# Ethernet.net
KiCad netlist of a schematic drawn in Altium Designer
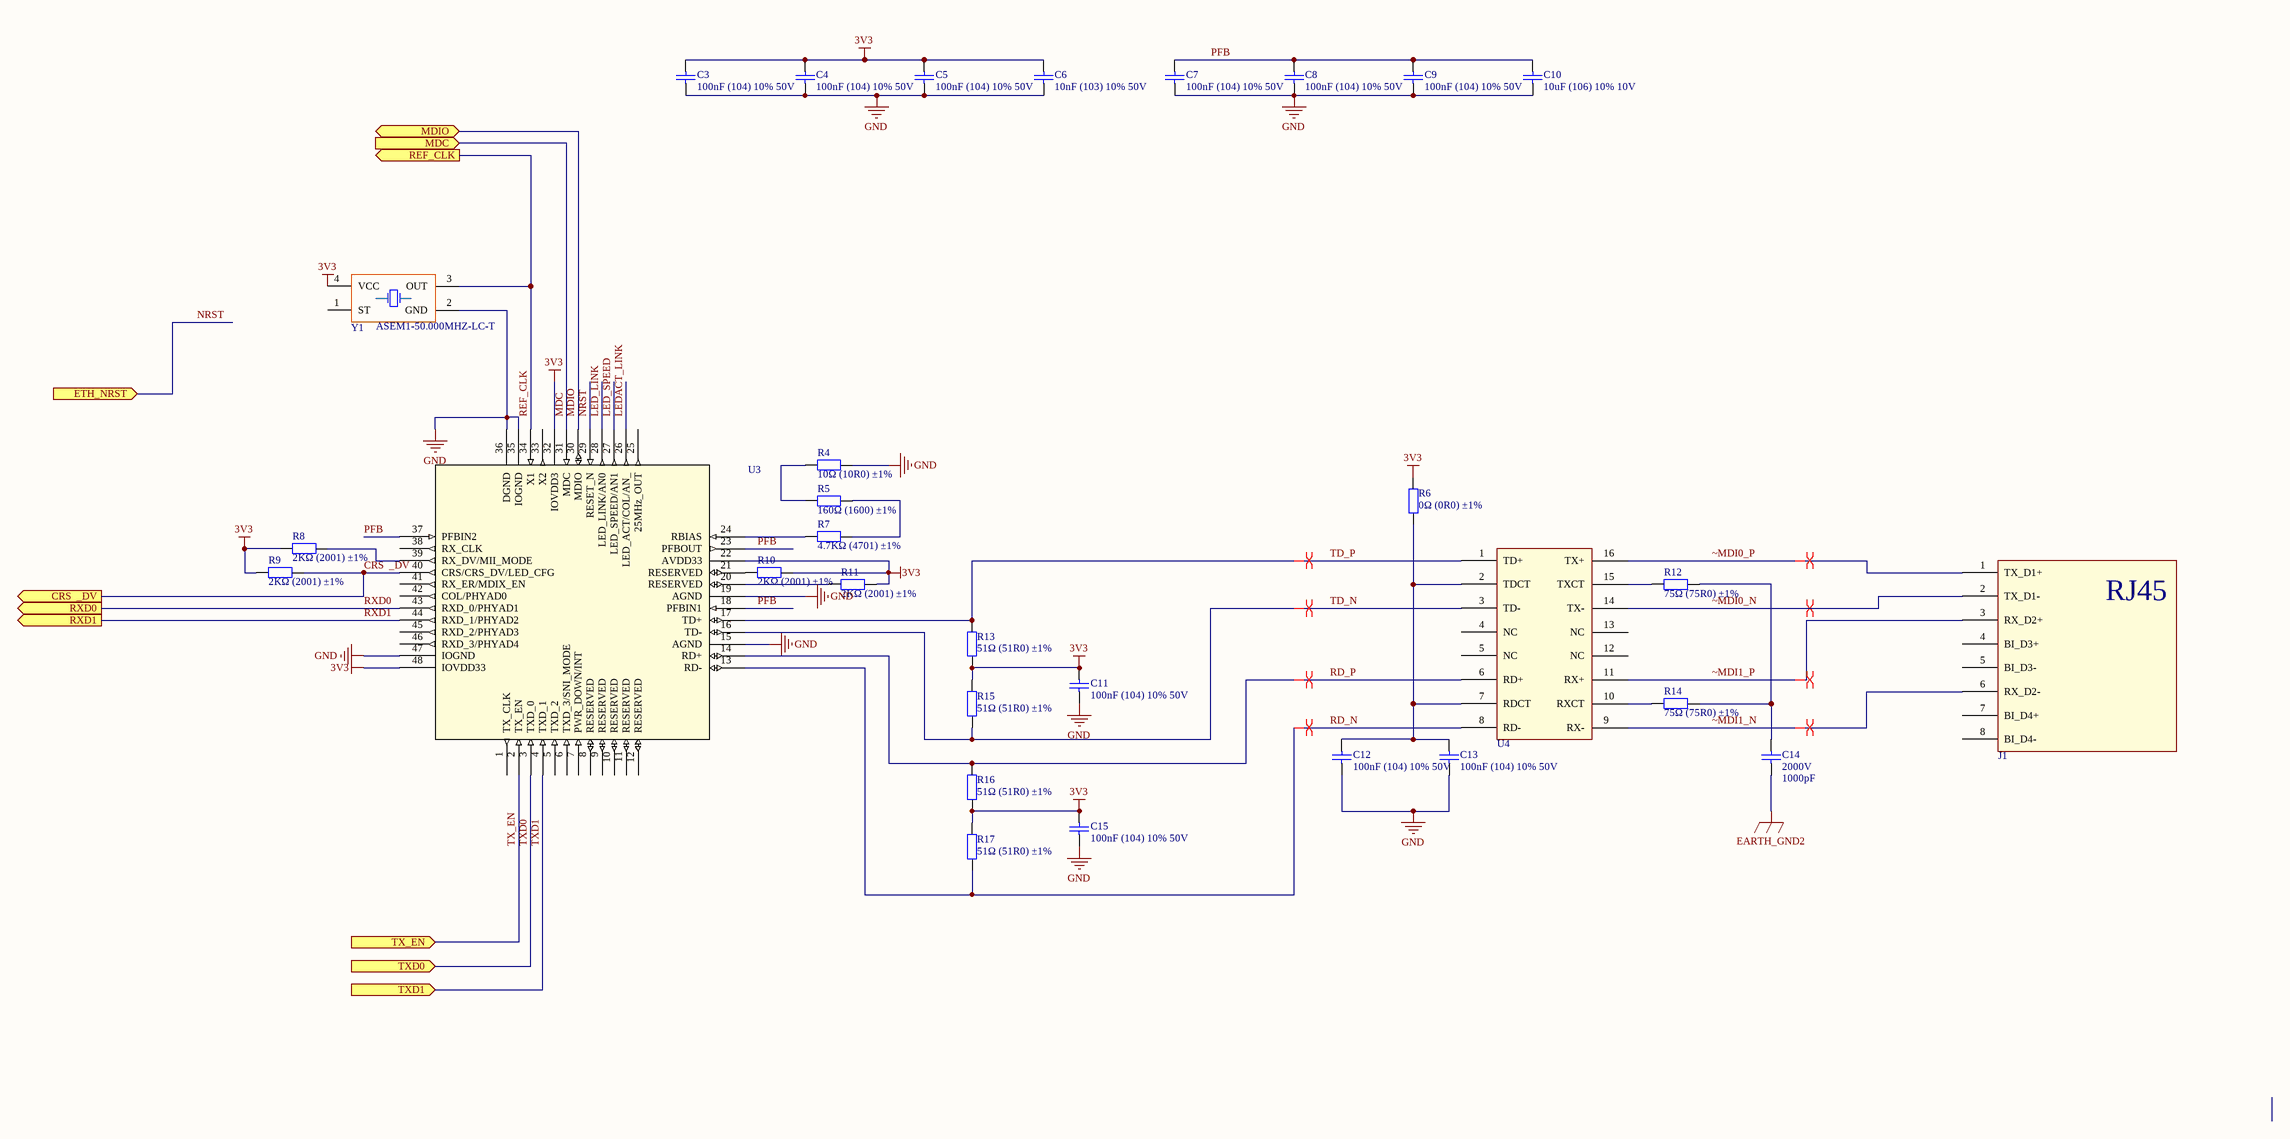
[diagram p0: Ethernet.SchDoc]

(export (version "E")
  (design (tool "Eeschema 10.0.6"))
  (components
    (comp (ref "C3")
      (value "100nF (104) 10% 50V")
      (footprint "0603_C")
      (description "贴片电容")
      (libsource (lib "Miscellaneous Devices LC") (part "0603 100nF (104) 10% 50V"))
    )
    (comp (ref "C4")
      (value "100nF (104) 10% 50V")
      (footprint "0603_C")
      (description "贴片电容")
      (libsource (lib "Miscellaneous Devices LC") (part "0603 100nF (104) 10% 50V"))
    )
    (comp (ref "C5")
      (value "100nF (104) 10% 50V")
      (footprint "0603_C")
      (description "贴片电容")
      (libsource (lib "Miscellaneous Devices LC") (part "0603 100nF (104) 10% 50V"))
    )
    (comp (ref "C6")
      (value "10nF (103) 10% 50V")
      (footprint "0603_C")
      (description "贴片电容")
      (libsource (lib "Miscellaneous Devices LC") (part "0603 10nF (103) 10% 50V"))
    )
    (comp (ref "C7")
      (value "100nF (104) 10% 50V")
      (footprint "0603_C")
      (description "贴片电容")
      (libsource (lib "Miscellaneous Devices LC") (part "0603 100nF (104) 10% 50V"))
    )
    (comp (ref "C8")
      (value "100nF (104) 10% 50V")
      (footprint "0603_C")
      (description "贴片电容")
      (libsource (lib "Miscellaneous Devices LC") (part "0603 100nF (104) 10% 50V"))
    )
    (comp (ref "C9")
      (value "100nF (104) 10% 50V")
      (footprint "0603_C")
      (description "贴片电容")
      (libsource (lib "Miscellaneous Devices LC") (part "0603 100nF (104) 10% 50V"))
    )
    (comp (ref "C10")
      (value "10uF (106) 10% 10V")
      (footprint "0603_C")
      (description "贴片电容")
      (libsource (lib "Miscellaneous Devices LC") (part "0603 10uF (106) 10% 10V"))
    )
    (comp (ref "C11")
      (value "100nF (104) 10% 50V")
      (footprint "0603_C")
      (description "贴片电容")
      (libsource (lib "Miscellaneous Devices LC") (part "0603 100nF (104) 10% 50V"))
    )
    (comp (ref "C12")
      (value "100nF (104) 10% 50V")
      (footprint "0603_C")
      (description "贴片电容")
      (libsource (lib "Miscellaneous Devices LC") (part "0603 100nF (104) 10% 50V"))
    )
    (comp (ref "C13")
      (value "100nF (104) 10% 50V")
      (footprint "0603_C")
      (description "贴片电容")
      (libsource (lib "Miscellaneous Devices LC") (part "0603 100nF (104) 10% 50V"))
    )
    (comp (ref "C14")
      (value "2000V")
      (footprint "CAP1210N")
      (description "CAP 1000pF ±10% 2000V (2kV) Ceramic Capacitor X7R 1210 (3225 Metric)")
      (fields
        (field (name "ALTIUM_VALUE") "1000pF")
        (field (name "MANUFACTURER") "Samsung Electro-Mechanics")
        (field (name "MANUFACTURER PART NUMBER") "CL32B102KJFNNNE")
      )
      (libsource (lib "RoboteX") (part "Cap Non-Polar"))
    )
    (comp (ref "C15")
      (value "100nF (104) 10% 50V")
      (footprint "0603_C")
      (description "贴片电容")
      (libsource (lib "Miscellaneous Devices LC") (part "0603 100nF (104) 10% 50V"))
    )
    (comp (ref "J1")
      (value "Jack Modular Connector 8p8c (RJ45, Ethernet) Vertical Unshielded Cat3")
      (footprint "RJ45-5556416-1")
      (description "RJ45 connector 180 degrees")
      (fields (field (name "PART NUMBER") "5556416-1") (field (name "MANUFACTURER") "TE"))
      (libsource (lib "RoboteX") (part "RJ45_180"))
    )
    (comp (ref "R4")
      (value "10Ω (10R0) ±1%")
      (footprint "0603_R")
      (description "贴片电阻")
      (libsource (lib "Miscellaneous Devices LC") (part "0603 10Ω (10R0) 1%"))
    )
    (comp (ref "R5")
      (value "160Ω (1600) ±1%")
      (footprint "0603_R")
      (description "贴片电阻")
      (libsource (lib "Miscellaneous Devices LC") (part "0603 160Ω (1600) 1%"))
    )
    (comp (ref "R6")
      (value "0Ω (0R0) ±1%")
      (footprint "0603_R")
      (description "贴片电阻")
      (libsource (lib "Miscellaneous Devices LC") (part "0603 0Ω (0R0) 1%"))
    )
    (comp (ref "R7")
      (value "4.7KΩ (4701) ±1%")
      (footprint "0603_R")
      (description "贴片电阻")
      (libsource (lib "Miscellaneous Devices LC") (part "0603 4.7KΩ (4701) 1%"))
    )
    (comp (ref "R8")
      (value "2KΩ (2001) ±1%")
      (footprint "0603_R")
      (description "贴片电阻")
      (libsource (lib "Miscellaneous Devices LC") (part "0603 2KΩ (2001) 1%"))
    )
    (comp (ref "R9")
      (value "2KΩ (2001) ±1%")
      (footprint "0603_R")
      (description "贴片电阻")
      (libsource (lib "Miscellaneous Devices LC") (part "0603 2KΩ (2001) 1%"))
    )
    (comp (ref "R10")
      (value "2KΩ (2001) ±1%")
      (footprint "0603_R")
      (description "贴片电阻")
      (libsource (lib "Miscellaneous Devices LC") (part "0603 2KΩ (2001) 1%"))
    )
    (comp (ref "R11")
      (value "2KΩ (2001) ±1%")
      (footprint "0603_R")
      (description "贴片电阻")
      (libsource (lib "Miscellaneous Devices LC") (part "0603 2KΩ (2001) 1%"))
    )
    (comp (ref "R12")
      (value "75Ω (75R0) ±1%")
      (footprint "0603_R")
      (description "贴片电阻")
      (libsource (lib "Miscellaneous Devices LC") (part "0603 75Ω (75R0) 1%"))
    )
    (comp (ref "R13")
      (value "51Ω (51R0) ±1%")
      (footprint "0603_R")
      (description "贴片电阻")
      (libsource (lib "Miscellaneous Devices LC") (part "0603 51Ω (51R0) 1%"))
    )
    (comp (ref "R14")
      (value "75Ω (75R0) ±1%")
      (footprint "0603_R")
      (description "贴片电阻")
      (libsource (lib "Miscellaneous Devices LC") (part "0603 75Ω (75R0) 1%"))
    )
    (comp (ref "R15")
      (value "51Ω (51R0) ±1%")
      (footprint "0603_R")
      (description "贴片电阻")
      (libsource (lib "Miscellaneous Devices LC") (part "0603 51Ω (51R0) 1%"))
    )
    (comp (ref "R16")
      (value "51Ω (51R0) ±1%")
      (footprint "0603_R")
      (description "贴片电阻")
      (libsource (lib "Miscellaneous Devices LC") (part "0603 51Ω (51R0) 1%"))
    )
    (comp (ref "R17")
      (value "51Ω (51R0) ±1%")
      (footprint "0603_R")
      (description "贴片电阻")
      (libsource (lib "Miscellaneous Devices LC") (part "0603 51Ω (51R0) 1%"))
    )
    (comp (ref "U3")
      (value "IC TXRX ETHERNET 48LQFP")
      (footprint "48-LQFP")
      (fields
        (field (name "PART NUMBER") "DP83848CVVX/NOPB")
        (field (name "MANUFACTURER") "Texas Instruments")
      )
      (libsource (lib "RoboteX") (part "DP83848CVV"))
    )
    (comp (ref "U4")
      (value "TRANSFORMER")
      (footprint "Bel_transformer")
      (description "MODULE XFRMR LAN 10/100B-TX SMD")
      (fields
        (field (name "MANUFACTURER") "Bel Fuse Inc.")
        (field (name "MANUFACTURER PART NUMBER") "S558-5999-U7-F")
      )
      (libsource (lib "RoboteX") (part "Transformer"))
    )
    (comp (ref "Y1")
      (value "Oscillator")
      (footprint "SMD-3225")
      (description "OSC MEMS 50.000MHZ CMOS SMD")
      (fields
        (field (name "PART NUMBER") "ASEM1-50.000MHZ-LC-T")
        (field (name "MANUFACTURER") "Abracon LLC")
        (field (name "MANUFACTURER PART NUMBER") "ASEM1-50.000MHZ-LC-T")
      )
      (libsource (lib "RoboteX") (part "SPXO"))
    )
  )
  (nets
    (net (code "1") (name "/CRS  _DV") (class "Default")
      (node (ref "R9") (pin "1") (pinfunction "1_1") (pintype "passive"))
      (node (ref "U3") (pin "40") (pinfunction "CRS/CRS_DV/LED_CFG_40") (pintype "output"))
    )
    (net (code "2") (name "/LEDACT_LINK") (class "Default")
      (node (ref "U3") (pin "26") (pinfunction "LED_ACT/COL/AN__26") (pintype "output"))
    )
    (net (code "3") (name "/LED_LINK") (class "Default")
      (node (ref "U3") (pin "28") (pinfunction "LED_LINK/AN0_28") (pintype "output"))
    )
    (net (code "4") (name "/LED_SPEED") (class "Default")
      (node (ref "U3") (pin "27") (pinfunction "LED_SPEED/AN1_27") (pintype "output"))
    )
    (net (code "5") (name "/MDC") (class "Default")
      (node (ref "U3") (pin "31") (pinfunction "MDC_31") (pintype "input"))
    )
    (net (code "6") (name "/MDIO") (class "Default")
      (node (ref "U3") (pin "30") (pinfunction "MDIO_30") (pintype "bidirectional"))
    )
    (net (code "7") (name "/NRST") (class "Default")
      (node (ref "U3") (pin "29") (pinfunction "RESET_N_29") (pintype "input"))
    )
    (net (code "8") (name "/PFB") (class "Default")
      (node (ref "C10") (pin "2") (pinfunction "2_2") (pintype "passive"))
      (node (ref "C7") (pin "2") (pinfunction "2_2") (pintype "passive"))
      (node (ref "C8") (pin "2") (pinfunction "2_2") (pintype "passive"))
      (node (ref "C9") (pin "2") (pinfunction "2_2") (pintype "passive"))
      (node (ref "U3") (pin "18") (pinfunction "PFBIN1_18") (pintype "input"))
      (node (ref "U3") (pin "23") (pinfunction "PFBOUT_23") (pintype "output"))
      (node (ref "U3") (pin "37") (pinfunction "PFBIN2_37") (pintype "input"))
    )
    (net (code "9") (name "/RD_N") (class "Default")
      (node (ref "R17") (pin "1") (pinfunction "1_1") (pintype "passive"))
      (node (ref "U3") (pin "13") (pinfunction "RD-_13") (pintype "bidirectional"))
      (node (ref "U4") (pin "8") (pinfunction "RD-_8") (pintype "passive"))
    )
    (net (code "10") (name "/RD_P") (class "Default")
      (node (ref "R16") (pin "2") (pinfunction "2_2") (pintype "passive"))
      (node (ref "U3") (pin "14") (pinfunction "RD+_14") (pintype "bidirectional"))
      (node (ref "U4") (pin "6") (pinfunction "RD+_6") (pintype "passive"))
    )
    (net (code "11") (name "/REF_CLK") (class "Default")
      (node (ref "U3") (pin "34") (pinfunction "X1_34") (pintype "input"))
      (node (ref "Y1") (pin "3") (pinfunction "OUT_3") (pintype "passive"))
    )
    (net (code "12") (name "/RXD0") (class "Default")
      (node (ref "U3") (pin "43") (pinfunction "RXD_0/PHYAD1_43") (pintype "output"))
    )
    (net (code "13") (name "/RXD1") (class "Default")
      (node (ref "U3") (pin "44") (pinfunction "RXD_1/PHYAD2_44") (pintype "output"))
    )
    (net (code "14") (name "/TD_N") (class "Default")
      (node (ref "R15") (pin "1") (pinfunction "1_1") (pintype "passive"))
      (node (ref "U3") (pin "16") (pinfunction "TD-_16") (pintype "bidirectional"))
      (node (ref "U4") (pin "3") (pinfunction "TD-_3") (pintype "passive"))
    )
    (net (code "15") (name "/TD_P") (class "Default")
      (node (ref "R13") (pin "2") (pinfunction "2_2") (pintype "passive"))
      (node (ref "U3") (pin "17") (pinfunction "TD+_17") (pintype "bidirectional"))
      (node (ref "U4") (pin "1") (pinfunction "TD+_1") (pintype "passive"))
    )
    (net (code "16") (name "/TXD0") (class "Default")
      (node (ref "U3") (pin "3") (pinfunction "TXD_0_3") (pintype "input"))
    )
    (net (code "17") (name "/TXD1") (class "Default")
      (node (ref "U3") (pin "4") (pinfunction "TXD_1_4") (pintype "input"))
    )
    (net (code "18") (name "/TX_EN") (class "Default")
      (node (ref "U3") (pin "2") (pinfunction "TX_EN_2") (pintype "input"))
    )
    (net (code "19") (name "/~MDI0_N") (class "Default")
      (node (ref "J1") (pin "2") (pinfunction "TX_D1-_2") (pintype "passive"))
      (node (ref "U4") (pin "14") (pinfunction "TX-_14") (pintype "passive"))
    )
    (net (code "20") (name "/~MDI0_P") (class "Default")
      (node (ref "J1") (pin "1") (pinfunction "TX_D1+_1") (pintype "passive"))
      (node (ref "U4") (pin "16") (pinfunction "TX+_16") (pintype "passive"))
    )
    (net (code "21") (name "/~MDI1_N") (class "Default")
      (node (ref "J1") (pin "6") (pinfunction "RX_D2-_6") (pintype "passive"))
      (node (ref "U4") (pin "9") (pinfunction "RX-_9") (pintype "passive"))
    )
    (net (code "22") (name "/~MDI1_P") (class "Default")
      (node (ref "J1") (pin "3") (pinfunction "RX_D2+_3") (pintype "passive"))
      (node (ref "U4") (pin "11") (pinfunction "RX+_11") (pintype "passive"))
    )
    (net (code "23") (name "3V3") (class "Default")
      (node (ref "C11") (pin "2") (pinfunction "2_2") (pintype "passive"))
      (node (ref "C15") (pin "2") (pinfunction "2_2") (pintype "passive"))
      (node (ref "C3") (pin "2") (pinfunction "2_2") (pintype "passive"))
      (node (ref "C4") (pin "2") (pinfunction "2_2") (pintype "passive"))
      (node (ref "C5") (pin "2") (pinfunction "2_2") (pintype "passive"))
      (node (ref "C6") (pin "2") (pinfunction "2_2") (pintype "passive"))
      (node (ref "R10") (pin "1") (pinfunction "1_1") (pintype "passive"))
      (node (ref "R11") (pin "1") (pinfunction "1_1") (pintype "passive"))
      (node (ref "R13") (pin "1") (pinfunction "1_1") (pintype "passive"))
      (node (ref "R15") (pin "2") (pinfunction "2_2") (pintype "passive"))
      (node (ref "R16") (pin "1") (pinfunction "1_1") (pintype "passive"))
      (node (ref "R17") (pin "2") (pinfunction "2_2") (pintype "passive"))
      (node (ref "R6") (pin "2") (pinfunction "2_2") (pintype "passive"))
      (node (ref "R8") (pin "2") (pinfunction "2_2") (pintype "passive"))
      (node (ref "R9") (pin "2") (pinfunction "2_2") (pintype "passive"))
      (node (ref "U3") (pin "22") (pinfunction "AVDD33_22") (pintype "power_in"))
      (node (ref "U3") (pin "32") (pinfunction "IOVDD3_32") (pintype "power_in"))
      (node (ref "U3") (pin "48") (pinfunction "IOVDD33_48") (pintype "power_in"))
      (node (ref "Y1") (pin "4") (pinfunction "VCC_4") (pintype "passive"))
    )
    (net (code "24") (name "EARTH_GND2") (class "Default")
      (node (ref "C14") (pin "1") (pinfunction "1_1") (pintype "passive"))
    )
    (net (code "25") (name "GND") (class "Default")
      (node (ref "C10") (pin "1") (pinfunction "1_1") (pintype "passive"))
      (node (ref "C11") (pin "1") (pinfunction "1_1") (pintype "passive"))
      (node (ref "C12") (pin "2") (pinfunction "2_2") (pintype "passive"))
      (node (ref "C13") (pin "1") (pinfunction "1_1") (pintype "passive"))
      (node (ref "C15") (pin "1") (pinfunction "1_1") (pintype "passive"))
      (node (ref "C3") (pin "1") (pinfunction "1_1") (pintype "passive"))
      (node (ref "C4") (pin "1") (pinfunction "1_1") (pintype "passive"))
      (node (ref "C5") (pin "1") (pinfunction "1_1") (pintype "passive"))
      (node (ref "C6") (pin "1") (pinfunction "1_1") (pintype "passive"))
      (node (ref "C7") (pin "1") (pinfunction "1_1") (pintype "passive"))
      (node (ref "C8") (pin "1") (pinfunction "1_1") (pintype "passive"))
      (node (ref "C9") (pin "1") (pinfunction "1_1") (pintype "passive"))
      (node (ref "R4") (pin "2") (pinfunction "2_2") (pintype "passive"))
      (node (ref "U3") (pin "15") (pinfunction "AGND_15") (pintype "power_in"))
      (node (ref "U3") (pin "19") (pinfunction "AGND_19") (pintype "power_in"))
      (node (ref "U3") (pin "35") (pinfunction "IOGND_35") (pintype "power_in"))
      (node (ref "U3") (pin "36") (pinfunction "DGND_36") (pintype "power_in"))
      (node (ref "U3") (pin "47") (pinfunction "IOGND_47") (pintype "power_in"))
      (node (ref "Y1") (pin "2") (pinfunction "GND_2") (pintype "passive"))
    )
    (net (code "26") (name "Net-(C14-Pad2)") (class "Default")
      (node (ref "C14") (pin "2") (pinfunction "2_2") (pintype "passive"))
      (node (ref "R12") (pin "2") (pinfunction "2_2") (pintype "passive"))
      (node (ref "R14") (pin "2") (pinfunction "2_2") (pintype "passive"))
    )
    (net (code "27") (name "Net-(R4-Pad1)") (class "Default")
      (node (ref "R4") (pin "1") (pinfunction "1_1") (pintype "passive"))
      (node (ref "R5") (pin "1") (pinfunction "1_1") (pintype "passive"))
    )
    (net (code "28") (name "Net-(R5-Pad2)") (class "Default")
      (node (ref "R5") (pin "2") (pinfunction "2_2") (pintype "passive"))
      (node (ref "R7") (pin "2") (pinfunction "2_2") (pintype "passive"))
    )
    (net (code "29") (name "Net-(R10-Pad2)") (class "Default")
      (node (ref "R10") (pin "2") (pinfunction "2_2") (pintype "passive"))
      (node (ref "U3") (pin "21") (pinfunction "RESERVED_21") (pintype "bidirectional"))
    )
    (net (code "30") (name "Net-(R11-Pad2)") (class "Default")
      (node (ref "R11") (pin "2") (pinfunction "2_2") (pintype "passive"))
      (node (ref "U3") (pin "20") (pinfunction "RESERVED_20") (pintype "bidirectional"))
    )
    (net (code "31") (name "Net-(U3-RBIAS)") (class "Default")
      (node (ref "R7") (pin "1") (pinfunction "1_1") (pintype "passive"))
      (node (ref "U3") (pin "24") (pinfunction "RBIAS_24") (pintype "input"))
    )
    (net (code "32") (name "Net-(U3-RX_DV{slash}MII_MODE)") (class "Default")
      (node (ref "R8") (pin "1") (pinfunction "1_1") (pintype "passive"))
      (node (ref "U3") (pin "39") (pinfunction "RX_DV/MII_MODE_39") (pintype "output"))
    )
    (net (code "33") (name "Net-(U4-RDCT)") (class "Default")
      (node (ref "C12") (pin "1") (pinfunction "1_1") (pintype "passive"))
      (node (ref "C13") (pin "2") (pinfunction "2_2") (pintype "passive"))
      (node (ref "R6") (pin "1") (pinfunction "1_1") (pintype "passive"))
      (node (ref "U4") (pin "2") (pinfunction "TDCT_2") (pintype "passive"))
      (node (ref "U4") (pin "7") (pinfunction "RDCT_7") (pintype "passive"))
    )
    (net (code "34") (name "Net-(U4-RXCT)") (class "Default")
      (node (ref "R14") (pin "1") (pinfunction "1_1") (pintype "passive"))
      (node (ref "U4") (pin "10") (pinfunction "RXCT_10") (pintype "passive"))
    )
    (net (code "35") (name "Net-(U4-TXCT)") (class "Default")
      (node (ref "R12") (pin "1") (pinfunction "1_1") (pintype "passive"))
      (node (ref "U4") (pin "15") (pinfunction "TXCT_15") (pintype "passive"))
    )
    (net (code "36") (name "unconnected-(J1-BI_D3+-Pad4)") (class "Default")
      (node (ref "J1") (pin "4") (pinfunction "BI_D3+_4") (pintype "passive"))
    )
    (net (code "37") (name "unconnected-(J1-BI_D3--Pad5)") (class "Default")
      (node (ref "J1") (pin "5") (pinfunction "BI_D3-_5") (pintype "passive"))
    )
    (net (code "38") (name "unconnected-(J1-BI_D4+-Pad7)") (class "Default")
      (node (ref "J1") (pin "7") (pinfunction "BI_D4+_7") (pintype "passive"))
    )
    (net (code "39") (name "unconnected-(J1-BI_D4--Pad8)") (class "Default")
      (node (ref "J1") (pin "8") (pinfunction "BI_D4-_8") (pintype "passive"))
    )
    (net (code "40") (name "unconnected-(U3-25MHz_OUT-Pad25)") (class "Default")
      (node (ref "U3") (pin "25") (pinfunction "25MHz_OUT_25") (pintype "output"))
    )
    (net (code "41") (name "unconnected-(U3-COL{slash}PHYAD0-Pad42)") (class "Default")
      (node (ref "U3") (pin "42") (pinfunction "COL/PHYAD0_42") (pintype "output"))
    )
    (net (code "42") (name "unconnected-(U3-PWR_DOWN{slash}INT-Pad7)") (class "Default")
      (node (ref "U3") (pin "7") (pinfunction "PWR_DOWN/INT_7") (pintype "input"))
    )
    (net (code "43") (name "unconnected-(U3-RESERVED-Pad8)") (class "Default")
      (node (ref "U3") (pin "8") (pinfunction "RESERVED_8") (pintype "bidirectional"))
    )
    (net (code "44") (name "unconnected-(U3-RESERVED-Pad9)") (class "Default")
      (node (ref "U3") (pin "9") (pinfunction "RESERVED_9") (pintype "bidirectional"))
    )
    (net (code "45") (name "unconnected-(U3-RESERVED-Pad10)") (class "Default")
      (node (ref "U3") (pin "10") (pinfunction "RESERVED_10") (pintype "bidirectional"))
    )
    (net (code "46") (name "unconnected-(U3-RESERVED-Pad11)") (class "Default")
      (node (ref "U3") (pin "11") (pinfunction "RESERVED_11") (pintype "bidirectional"))
    )
    (net (code "47") (name "unconnected-(U3-RESERVED-Pad12)") (class "Default")
      (node (ref "U3") (pin "12") (pinfunction "RESERVED_12") (pintype "bidirectional"))
    )
    (net (code "48") (name "unconnected-(U3-RXD_2{slash}PHYAD3-Pad45)") (class "Default")
      (node (ref "U3") (pin "45") (pinfunction "RXD_2/PHYAD3_45") (pintype "output"))
    )
    (net (code "49") (name "unconnected-(U3-RXD_3{slash}PHYAD4-Pad46)") (class "Default")
      (node (ref "U3") (pin "46") (pinfunction "RXD_3/PHYAD4_46") (pintype "output"))
    )
    (net (code "50") (name "unconnected-(U3-RX_CLK-Pad38)") (class "Default")
      (node (ref "U3") (pin "38") (pinfunction "RX_CLK_38") (pintype "output"))
    )
    (net (code "51") (name "unconnected-(U3-RX_ER{slash}MDIX_EN-Pad41)") (class "Default")
      (node (ref "U3") (pin "41") (pinfunction "RX_ER/MDIX_EN_41") (pintype "output"))
    )
    (net (code "52") (name "unconnected-(U3-TXD_2-Pad5)") (class "Default")
      (node (ref "U3") (pin "5") (pinfunction "TXD_2_5") (pintype "input"))
    )
    (net (code "53") (name "unconnected-(U3-TXD_3{slash}SNI_MODE-Pad6)") (class "Default")
      (node (ref "U3") (pin "6") (pinfunction "TXD_3/SNI_MODE_6") (pintype "input"))
    )
    (net (code "54") (name "unconnected-(U3-TX_CLK-Pad1)") (class "Default")
      (node (ref "U3") (pin "1") (pinfunction "TX_CLK_1") (pintype "output"))
    )
    (net (code "55") (name "unconnected-(U3-X2-Pad33)") (class "Default")
      (node (ref "U3") (pin "33") (pinfunction "X2_33") (pintype "output"))
    )
    (net (code "56") (name "unconnected-(U4-NC-Pad4)") (class "Default")
      (node (ref "U4") (pin "4") (pinfunction "NC_4") (pintype "passive"))
    )
    (net (code "57") (name "unconnected-(U4-NC-Pad5)") (class "Default")
      (node (ref "U4") (pin "5") (pinfunction "NC_5") (pintype "passive"))
    )
    (net (code "58") (name "unconnected-(U4-NC-Pad12)") (class "Default")
      (node (ref "U4") (pin "12") (pinfunction "NC_12") (pintype "passive"))
    )
    (net (code "59") (name "unconnected-(U4-NC-Pad13)") (class "Default")
      (node (ref "U4") (pin "13") (pinfunction "NC_13") (pintype "passive"))
    )
    (net (code "60") (name "unconnected-(Y1-ST-Pad1)") (class "Default")
      (node (ref "Y1") (pin "1") (pinfunction "ST_1") (pintype "passive"))
    )
  )
)
